# S5_-_BLUETOOTH.net
KiCad netlist of a schematic drawn in Altium Designer
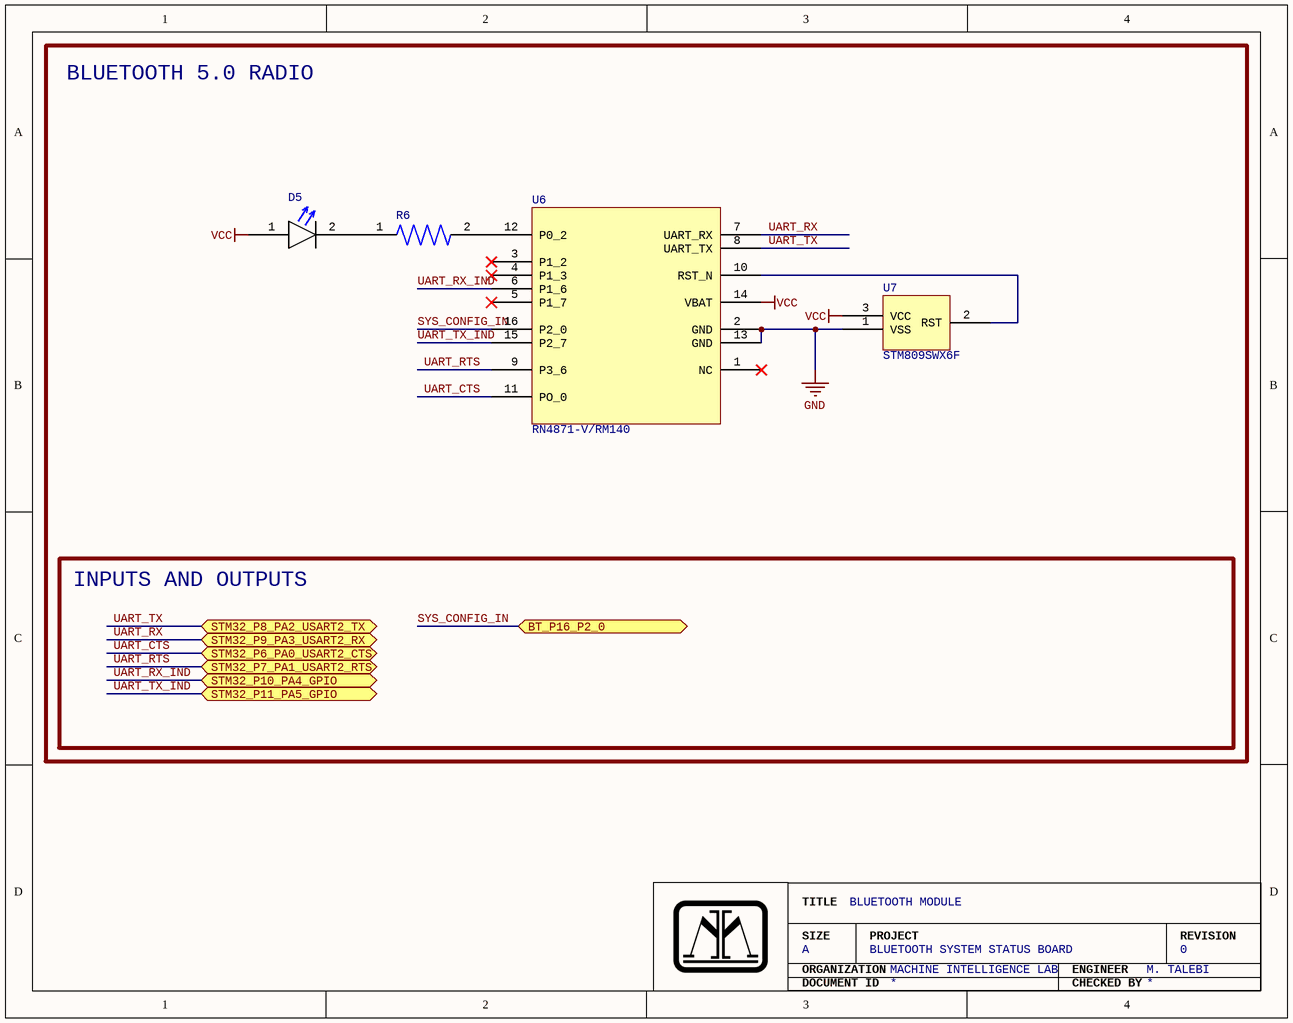
[diagram p0: S5 - BLUETOOTH.SchDoc]

(export (version "E")
  (design (tool "Eeschema 10.0.6"))
  (components
    (comp (ref "D5")
      (value "SLR343BC4T3F")
      (footprint "SLR343BC4T3F")
      (description "LED BLUE CLEAR T-1 T/H")
      (libsource (lib "Master") (part "SLR343BC4T3F"))
    )
    (comp (ref "R6")
      (value "CRCW0201330RFKED")
      (footprint "CRCW0201330RFKED")
      (description "RES SMD 330 OHM 1% 1/20W 0201")
      (fields (field (name "TOLERANCE") "±1%"))
      (libsource (lib "Master") (part "CRCW0201330RFKED"))
    )
    (comp (ref "U6")
      (value "RN4871-V/RM140")
      (footprint "RN4871-V/RM140")
      (description "RX TXRX MODULE BLE CHIP SMD")
      (fields (field (name "UTILIZED IC / PART") "RN4871"))
      (libsource (lib "Master") (part "RN4871-V/RM140"))
    )
    (comp (ref "U7")
      (value "STM809SWX6F")
      (footprint "STM809SWX6F")
      (description "IC SUPERVISOR 1 CHANNEL SOT23-3")
      (libsource (lib "Master") (part "STM809SWX6F"))
    )
  )
  (nets
    (net (code "1") (name "/SYS_CONFIG_IN") (class "Default")
      (node (ref "U6") (pin "16") (pinfunction "P2_0_16") (pintype "passive"))
    )
    (net (code "2") (name "/UART_CTS") (class "Default")
      (node (ref "U6") (pin "11") (pinfunction "PO_0_11") (pintype "passive"))
    )
    (net (code "3") (name "/UART_RTS") (class "Default")
      (node (ref "U6") (pin "9") (pinfunction "P3_6_9") (pintype "passive"))
    )
    (net (code "4") (name "/UART_RX") (class "Default")
      (node (ref "U6") (pin "7") (pinfunction "UART_RX_7") (pintype "passive"))
    )
    (net (code "5") (name "/UART_RX_IND") (class "Default")
      (node (ref "U6") (pin "6") (pinfunction "P1_6_6") (pintype "passive"))
    )
    (net (code "6") (name "/UART_TX") (class "Default")
      (node (ref "U6") (pin "8") (pinfunction "UART_TX_8") (pintype "passive"))
    )
    (net (code "7") (name "/UART_TX_IND") (class "Default")
      (node (ref "U6") (pin "15") (pinfunction "P2_7_15") (pintype "passive"))
    )
    (net (code "8") (name "GND") (class "Default")
      (node (ref "U6") (pin "13") (pinfunction "GND_13") (pintype "passive"))
      (node (ref "U6") (pin "2") (pinfunction "GND_2") (pintype "passive"))
      (node (ref "U7") (pin "1") (pinfunction "VSS_1") (pintype "passive"))
    )
    (net (code "9") (name "Net-(D5-+)") (class "Default")
      (node (ref "D5") (pin "2") (pinfunction "+_2") (pintype "passive"))
      (node (ref "R6") (pin "1") (pinfunction "1_1") (pintype "passive"))
    )
    (net (code "10") (name "Net-(U6-P0_2)") (class "Default")
      (node (ref "R6") (pin "2") (pinfunction "2_2") (pintype "passive"))
      (node (ref "U6") (pin "12") (pinfunction "P0_2_12") (pintype "passive"))
    )
    (net (code "11") (name "Net-(U6-RST_N)") (class "Default")
      (node (ref "U6") (pin "10") (pinfunction "RST_N_10") (pintype "passive"))
      (node (ref "U7") (pin "2") (pinfunction "RST_2") (pintype "passive"))
    )
    (net (code "12") (name "VCC") (class "Default")
      (node (ref "D5") (pin "1") (pinfunction "-_1") (pintype "passive"))
      (node (ref "U6") (pin "14") (pinfunction "VBAT_14") (pintype "passive"))
      (node (ref "U7") (pin "3") (pinfunction "VCC_3") (pintype "passive"))
    )
    (net (code "13") (name "unconnected-(U6-NC-Pad1)") (class "Default")
      (node (ref "U6") (pin "1") (pinfunction "NC_1") (pintype "passive+no_connect"))
    )
    (net (code "14") (name "unconnected-(U6-P1_2-Pad3)") (class "Default")
      (node (ref "U6") (pin "3") (pinfunction "P1_2_3") (pintype "passive+no_connect"))
    )
    (net (code "15") (name "unconnected-(U6-P1_3-Pad4)") (class "Default")
      (node (ref "U6") (pin "4") (pinfunction "P1_3_4") (pintype "passive+no_connect"))
    )
    (net (code "16") (name "unconnected-(U6-P1_7-Pad5)") (class "Default")
      (node (ref "U6") (pin "5") (pinfunction "P1_7_5") (pintype "passive+no_connect"))
    )
  )
)
